# EXCISS_HVU.net
KiCad netlist of a schematic drawn in EAGLE
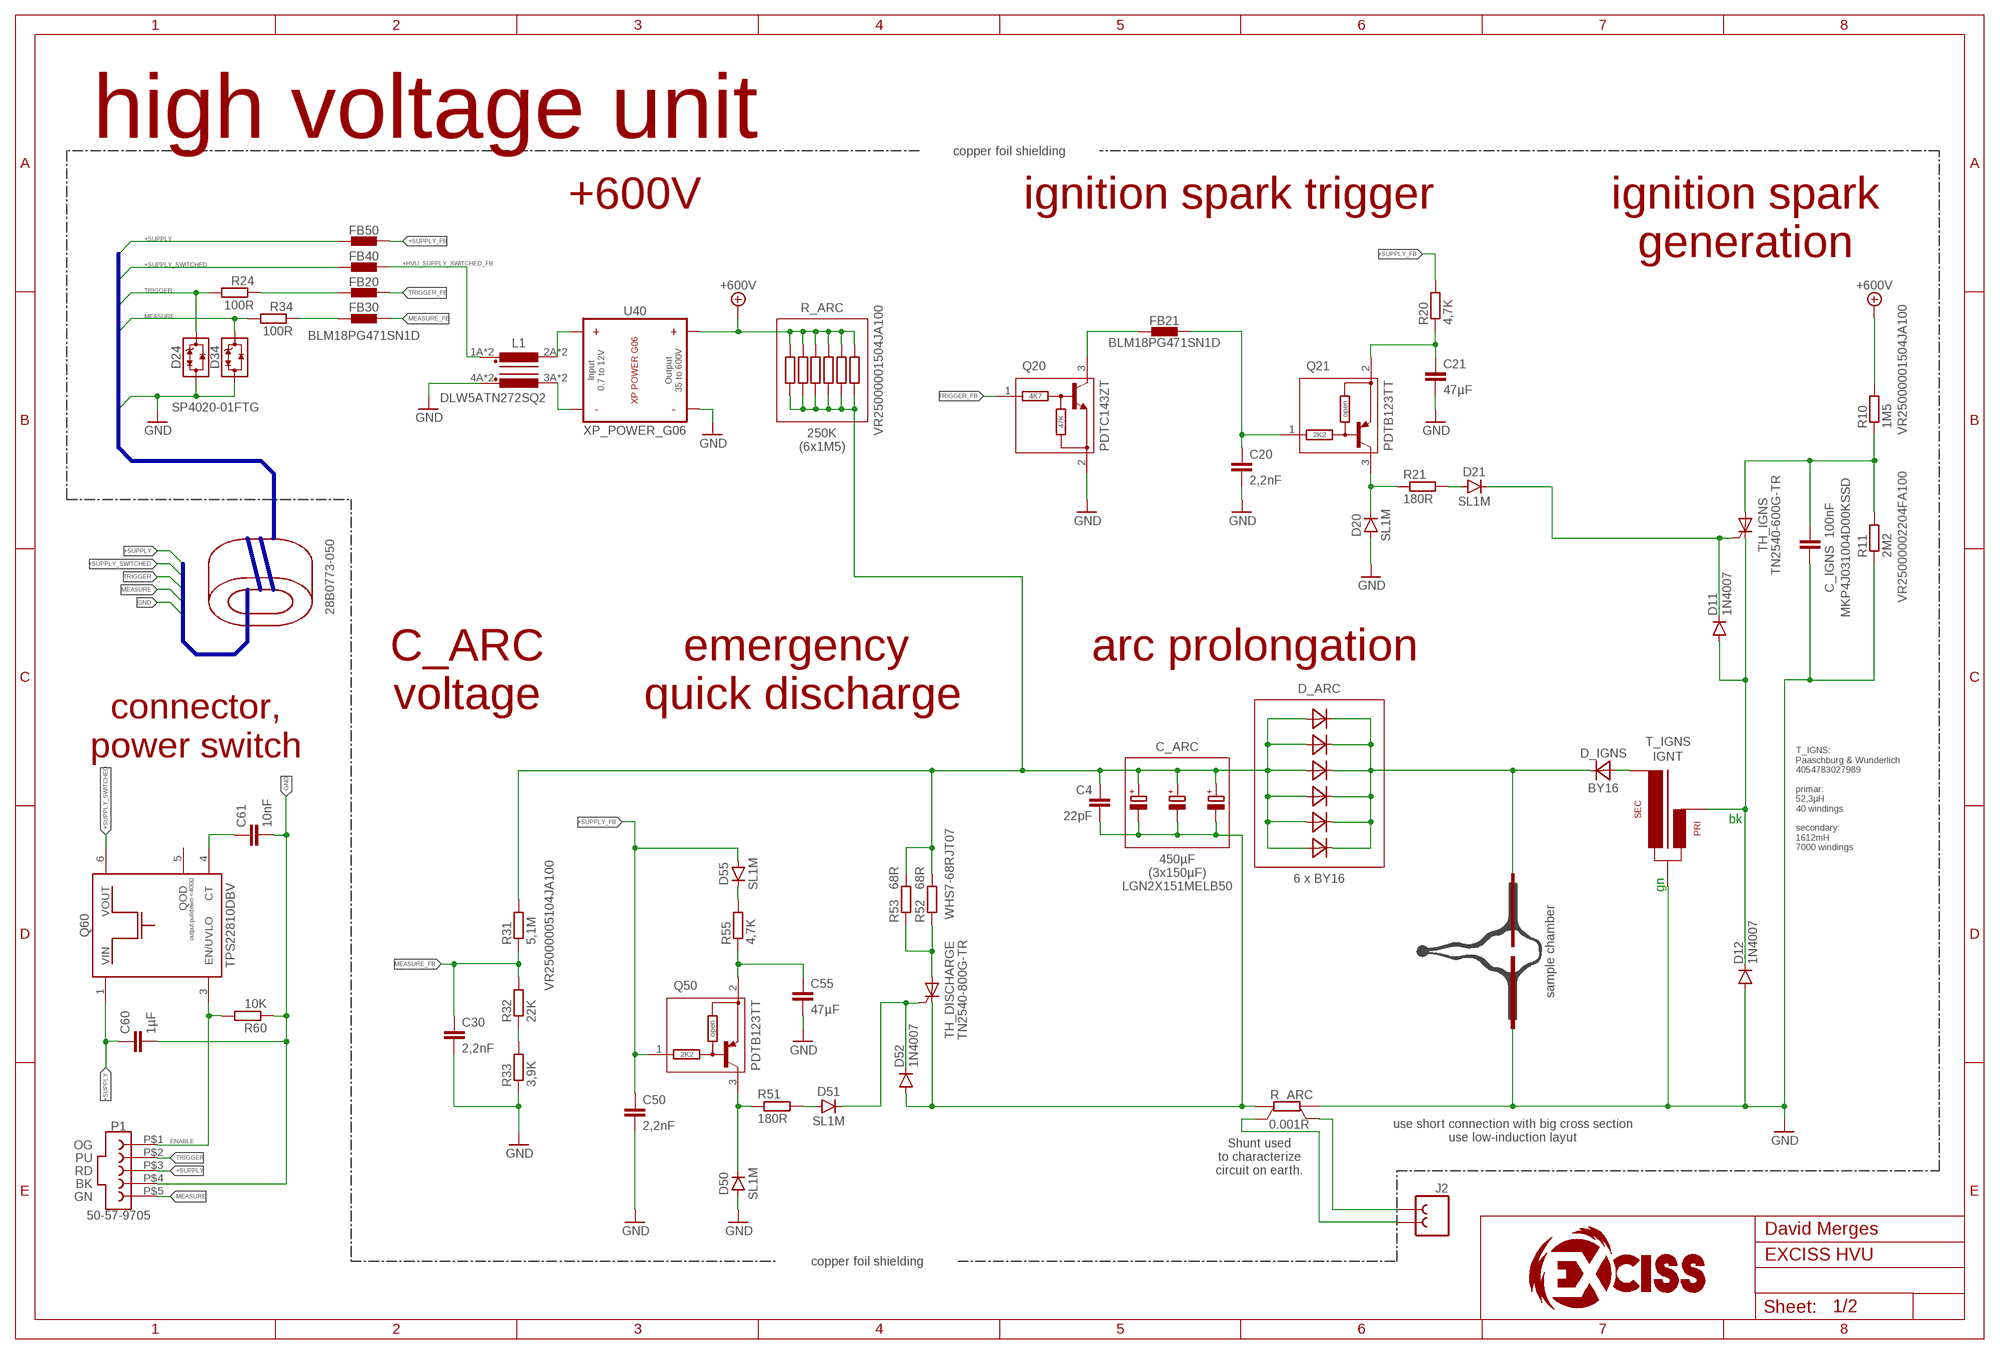
[diagram p0: schematic, sheet 1]

(export (version "E")
  (design (tool "Eeschema 10.0.6"))
  (components
    (comp (ref "C4")
      (value "22pF")
      (footprint "eagle-import:C0805")
      (libsource (lib "eagle-import") (part "C-EUC0805"))
    )
    (comp (ref "C20")
      (value "2,2nF")
      (footprint "eagle-import:C0805")
      (libsource (lib "eagle-import") (part "C-EUC0805"))
    )
    (comp (ref "C21")
      (value "47µF")
      (footprint "eagle-import:C1206")
      (libsource (lib "eagle-import") (part "C-EUC1206"))
    )
    (comp (ref "C30")
      (value "2,2nF")
      (footprint "eagle-import:C0805")
      (libsource (lib "eagle-import") (part "C-EUC0805"))
    )
    (comp (ref "C50")
      (value "2,2nF")
      (footprint "eagle-import:C0805")
      (libsource (lib "eagle-import") (part "C-EUC0805"))
    )
    (comp (ref "C55")
      (value "47µF")
      (footprint "eagle-import:C1206")
      (libsource (lib "eagle-import") (part "C-EUC1206"))
    )
    (comp (ref "C60")
      (value "1µF")
      (footprint "eagle-import:C0805")
      (libsource (lib "eagle-import") (part "C-EUC0805"))
    )
    (comp (ref "C61")
      (value "10nF")
      (footprint "eagle-import:C0603")
      (libsource (lib "eagle-import") (part "C-EUC0603"))
    )
    (comp (ref "C_ARC1")
      (value "150µF")
      (footprint "eagle-import:140CLH-1010")
      (libsource (lib "eagle-import") (part "CPOL-EU140CLH-1010"))
    )
    (comp (ref "C_ARC2")
      (value "150µF")
      (footprint "eagle-import:140CLH-1010")
      (libsource (lib "eagle-import") (part "CPOL-EU140CLH-1010"))
    )
    (comp (ref "C_ARC3")
      (value "150µF")
      (footprint "eagle-import:140CLH-1010")
      (libsource (lib "eagle-import") (part "CPOL-EU140CLH-1010"))
    )
    (comp (ref "C_IGNS")
      (value "100nF")
      (footprint "eagle-import:C025-024X044")
      (libsource (lib "eagle-import") (part "C-EU025-024X044"))
    )
    (comp (ref "D11")
      (value "1N4007")
      (footprint "eagle-import:DO41-10")
      (libsource (lib "eagle-import") (part "1N4007"))
    )
    (comp (ref "D12")
      (value "1N4007")
      (footprint "eagle-import:DO41-10")
      (libsource (lib "eagle-import") (part "1N4007"))
    )
    (comp (ref "D20")
      (value "SL1M")
      (footprint "eagle-import:SOD-123FL")
      (libsource (lib "eagle-import") (part "SL1M"))
    )
    (comp (ref "D21")
      (value "SL1M")
      (footprint "eagle-import:SOD-123FL")
      (libsource (lib "eagle-import") (part "SL1M"))
    )
    (comp (ref "D24")
      (value "SP4020-01FTG")
      (footprint "eagle-import:SOD-323")
      (libsource (lib "eagle-import") (part "SP4020-01FTG"))
    )
    (comp (ref "D34")
      (value "SP4020-01FTG")
      (footprint "eagle-import:SOD-323")
      (libsource (lib "eagle-import") (part "SP4020-01FTG"))
    )
    (comp (ref "D50")
      (value "SL1M")
      (footprint "eagle-import:SOD-123FL")
      (libsource (lib "eagle-import") (part "SL1M"))
    )
    (comp (ref "D51")
      (value "SL1M")
      (footprint "eagle-import:SOD-123FL")
      (libsource (lib "eagle-import") (part "SL1M"))
    )
    (comp (ref "D52")
      (value "1N4007")
      (footprint "eagle-import:DO41-10")
      (libsource (lib "eagle-import") (part "1N4007"))
    )
    (comp (ref "D55")
      (value "SL1M")
      (footprint "eagle-import:SOD-123FL")
      (libsource (lib "eagle-import") (part "SL1M"))
    )
    (comp (ref "D_ARC1")
      (value "BY16")
      (footprint "eagle-import:BY16")
      (libsource (lib "eagle-import") (part "BY16"))
    )
    (comp (ref "D_ARC2")
      (value "BY16")
      (footprint "eagle-import:BY16")
      (libsource (lib "eagle-import") (part "BY16"))
    )
    (comp (ref "D_ARC3")
      (value "BY16")
      (footprint "eagle-import:BY16")
      (libsource (lib "eagle-import") (part "BY16"))
    )
    (comp (ref "D_ARC4")
      (value "BY16")
      (footprint "eagle-import:BY16")
      (libsource (lib "eagle-import") (part "BY16"))
    )
    (comp (ref "D_ARC5")
      (value "BY16")
      (footprint "eagle-import:BY16")
      (libsource (lib "eagle-import") (part "BY16"))
    )
    (comp (ref "D_ARC6")
      (value "BY16")
      (footprint "eagle-import:BY16")
      (libsource (lib "eagle-import") (part "BY16"))
    )
    (comp (ref "D_IGNS")
      (value "BY16")
      (footprint "eagle-import:BY16")
      (libsource (lib "eagle-import") (part "BY16"))
    )
    (comp (ref "FB20")
      (value "BLM18PG471SN1D")
      (footprint "eagle-import:0402")
      (libsource (lib "eagle-import") (part "BLM15HB121SN1"))
    )
    (comp (ref "FB21")
      (value "BLM18PG471SN1D")
      (footprint "eagle-import:0402")
      (libsource (lib "eagle-import") (part "BLM15HB121SN1"))
    )
    (comp (ref "FB30")
      (value "BLM18PG471SN1D")
      (footprint "eagle-import:0402")
      (libsource (lib "eagle-import") (part "BLM15HB121SN1"))
    )
    (comp (ref "FB40")
      (value "BLM18PG471SN1D")
      (footprint "eagle-import:0402")
      (libsource (lib "eagle-import") (part "BLM15HB121SN1"))
    )
    (comp (ref "FB50")
      (value "BLM18PG471SN1D")
      (footprint "eagle-import:0402")
      (libsource (lib "eagle-import") (part "BLM15HB121SN1"))
    )
    (comp (ref "J2")
      (value "F02")
      (footprint "eagle-import:1X02")
      (libsource (lib "eagle-import") (part "F02"))
    )
    (comp (ref "L1")
      (value "DLW5ATN272SQ2")
      (footprint "eagle-import:DLW5AT")
      (libsource (lib "eagle-import") (part "DLW5ATN272SQ2"))
    )
    (comp (ref "P1")
      (value "50-57-9705")
      (footprint "eagle-import:DUMMY")
      (libsource (lib "eagle-import") (part "14-56-2054"))
    )
    (comp (ref "Q20")
      (value "PDTC143ZT")
      (footprint "eagle-import:SOT23-3")
      (libsource (lib "eagle-import") (part "PDTC143ZT"))
    )
    (comp (ref "Q21")
      (value "PDTB123TT")
      (footprint "eagle-import:SOT23-3")
      (libsource (lib "eagle-import") (part "PDTB123TT"))
    )
    (comp (ref "Q50")
      (value "PDTB123TT")
      (footprint "eagle-import:SOT23-3")
      (libsource (lib "eagle-import") (part "PDTB123TT"))
    )
    (comp (ref "Q60")
      (value "TPS22810DBV")
      (footprint "eagle-import:SOT23-6_DBV")
      (libsource (lib "eagle-import") (part "TPS22810DBV"))
    )
    (comp (ref "R10")
      (value "1M5")
      (footprint "eagle-import:0204_7")
      (libsource (lib "eagle-import") (part "R-EU_0204/7"))
    )
    (comp (ref "R11")
      (value "2M2")
      (footprint "eagle-import:0204_7")
      (libsource (lib "eagle-import") (part "R-EU_0204/7"))
    )
    (comp (ref "R20")
      (value "4,7K")
      (footprint "eagle-import:R0603")
      (libsource (lib "eagle-import") (part "R-EU_R0603"))
    )
    (comp (ref "R21")
      (value "180R")
      (footprint "eagle-import:R0603")
      (libsource (lib "eagle-import") (part "R-EU_R0603"))
    )
    (comp (ref "R24")
      (value "100R")
      (footprint "eagle-import:R0603")
      (libsource (lib "eagle-import") (part "R-EU_R0603"))
    )
    (comp (ref "R31")
      (value "5,1M")
      (footprint "eagle-import:0204_7")
      (libsource (lib "eagle-import") (part "R-EU_0204/7"))
    )
    (comp (ref "R32")
      (value "22K")
      (footprint "eagle-import:0204_7")
      (libsource (lib "eagle-import") (part "R-EU_0204/7"))
    )
    (comp (ref "R33")
      (value "3,9K")
      (footprint "eagle-import:0204_7")
      (libsource (lib "eagle-import") (part "R-EU_0204/7"))
    )
    (comp (ref "R34")
      (value "100R")
      (footprint "eagle-import:R0603")
      (libsource (lib "eagle-import") (part "R-EU_R0603"))
    )
    (comp (ref "R51")
      (value "180R")
      (footprint "eagle-import:R0603")
      (libsource (lib "eagle-import") (part "R-EU_R0603"))
    )
    (comp (ref "R52")
      (value "68R")
      (footprint "eagle-import:0204_7")
      (libsource (lib "eagle-import") (part "R-EU_0204/7"))
    )
    (comp (ref "R53")
      (value "68R")
      (footprint "eagle-import:0204_7")
      (libsource (lib "eagle-import") (part "R-EU_0204/7"))
    )
    (comp (ref "R55")
      (value "4,7K")
      (footprint "eagle-import:R0603")
      (libsource (lib "eagle-import") (part "R-EU_R0603"))
    )
    (comp (ref "R60")
      (value "10K")
      (footprint "eagle-import:R0805")
      (libsource (lib "eagle-import") (part "R-EU_R0805"))
    )
    (comp (ref "R_ARC")
      (value "0.001R")
      (footprint "eagle-import:SMV")
      (libsource (lib "eagle-import") (part "SMV"))
    )
    (comp (ref "R_ARC1")
      (value "1,5M")
      (footprint "eagle-import:0204_7")
      (libsource (lib "eagle-import") (part "R-EU_0204/7"))
    )
    (comp (ref "R_ARC2")
      (value "1,5M")
      (footprint "eagle-import:0204_7")
      (libsource (lib "eagle-import") (part "R-EU_0204/7"))
    )
    (comp (ref "R_ARC3")
      (value "1,5M")
      (footprint "eagle-import:0204_7")
      (libsource (lib "eagle-import") (part "R-EU_0204/7"))
    )
    (comp (ref "R_ARC4")
      (value "1,5M")
      (footprint "eagle-import:0204_7")
      (libsource (lib "eagle-import") (part "R-EU_0204/7"))
    )
    (comp (ref "R_ARC5")
      (value "1,5M")
      (footprint "eagle-import:0204_7")
      (libsource (lib "eagle-import") (part "R-EU_0204/7"))
    )
    (comp (ref "R_ARC6")
      (value "1,5M")
      (footprint "eagle-import:0204_7")
      (libsource (lib "eagle-import") (part "R-EU_0204/7"))
    )
    (comp (ref "TH_DISCHARGE")
      (value "TN2540-800G-TR")
      (footprint "eagle-import:D2PACK")
      (libsource (lib "eagle-import") (part "TN2540-600G-TR"))
    )
    (comp (ref "TH_IGNS")
      (value "TN2540-600G-TR")
      (footprint "eagle-import:D2PACK")
      (libsource (lib "eagle-import") (part "TN2540-600G-TR"))
    )
    (comp (ref "T_IGNS")
      (value "IGNT")
      (footprint "eagle-import:DUMMY")
      (libsource (lib "eagle-import") (part "IGNT"))
    )
    (comp (ref "U$2")
      (value "PROBENKAMMER")
      (footprint "eagle-import:DUMMY")
      (libsource (lib "eagle-import") (part "PROBENKAMMER"))
    )
    (comp (ref "U40")
      (value "XP_POWER_G06")
      (footprint "eagle-import:XP_POWER_G06")
      (libsource (lib "eagle-import") (part "XP_POWER_G06"))
    )
  )
  (nets
    (net (code "1") (name "+600V") (class "Default")
      (node (ref "R10") (pin "2") (pinfunction "2_2") (pintype "passive"))
      (node (ref "R_ARC1") (pin "2") (pinfunction "2_2") (pintype "passive"))
      (node (ref "R_ARC2") (pin "2") (pinfunction "2_2") (pintype "passive"))
      (node (ref "R_ARC3") (pin "2") (pinfunction "2_2") (pintype "passive"))
      (node (ref "R_ARC4") (pin "2") (pinfunction "2_2") (pintype "passive"))
      (node (ref "R_ARC5") (pin "2") (pinfunction "2_2") (pintype "passive"))
      (node (ref "R_ARC6") (pin "2") (pinfunction "2_2") (pintype "passive"))
      (node (ref "U40") (pin "3") (pinfunction "+VOUT_3") (pintype "passive"))
    )
    (net (code "2") (name "+HVU_SUPPLY_SWITCHED_FB") (class "Default")
      (node (ref "FB40") (pin "2") (pinfunction "2_2") (pintype "passive"))
      (node (ref "L1") (pin "1A") (pinfunction "1_1A") (pintype "passive"))
      (node (ref "L1") (pin "1B+") (pinfunction "1_1B+") (pintype "passive"))
    )
    (net (code "3") (name "+SUPPLY") (class "Default")
      (node (ref "C60") (pin "1") (pinfunction "1_1") (pintype "passive"))
      (node (ref "FB50") (pin "1") (pinfunction "1_1") (pintype "passive"))
      (node (ref "P1") (pin "P$3") (pinfunction "3_P$3") (pintype "passive"))
      (node (ref "Q60") (pin "1") (pinfunction "VIN_1") (pintype "power_in"))
    )
    (net (code "4") (name "+SUPPLY_FB") (class "Default")
      (node (ref "C50") (pin "1") (pinfunction "1_1") (pintype "passive"))
      (node (ref "D55") (pin "A") (pinfunction "A_A") (pintype "passive"))
      (node (ref "FB50") (pin "2") (pinfunction "2_2") (pintype "passive"))
      (node (ref "Q50") (pin "1") (pinfunction "B_1") (pintype "passive"))
      (node (ref "R20") (pin "2") (pinfunction "2_2") (pintype "passive"))
    )
    (net (code "5") (name "+SUPPLY_SWITCHED") (class "Default")
      (node (ref "FB40") (pin "1") (pinfunction "1_1") (pintype "passive"))
      (node (ref "Q60") (pin "6") (pinfunction "VOUT_6") (pintype "output"))
    )
    (net (code "7") (name "ENABLE") (class "Default")
      (node (ref "P1") (pin "P$1") (pinfunction "1_P$1") (pintype "passive"))
      (node (ref "Q60") (pin "3") (pinfunction "EN/UVLO_3") (pintype "input"))
      (node (ref "R60") (pin "2") (pinfunction "2_2") (pintype "passive"))
    )
    (net (code "8") (name "GND") (class "Default")
      (node (ref "C20") (pin "2") (pinfunction "2_2") (pintype "passive"))
      (node (ref "C21") (pin "2") (pinfunction "2_2") (pintype "passive"))
      (node (ref "C30") (pin "2") (pinfunction "2_2") (pintype "passive"))
      (node (ref "C50") (pin "2") (pinfunction "2_2") (pintype "passive"))
      (node (ref "C55") (pin "2") (pinfunction "2_2") (pintype "passive"))
      (node (ref "C60") (pin "2") (pinfunction "2_2") (pintype "passive"))
      (node (ref "C61") (pin "2") (pinfunction "2_2") (pintype "passive"))
      (node (ref "C_IGNS") (pin "2") (pinfunction "2_2") (pintype "passive"))
      (node (ref "D12") (pin "A") (pinfunction "A_A") (pintype "passive"))
      (node (ref "D20") (pin "A") (pinfunction "A_A") (pintype "passive"))
      (node (ref "D24") (pin "A") (pinfunction "2_A") (pintype "passive"))
      (node (ref "D34") (pin "A") (pinfunction "2_A") (pintype "passive"))
      (node (ref "D50") (pin "A") (pinfunction "A_A") (pintype "passive"))
      (node (ref "L1") (pin "4A") (pinfunction "4_4A") (pintype "passive"))
      (node (ref "L1") (pin "4B") (pinfunction "4_4B") (pintype "passive"))
      (node (ref "P1") (pin "P$4") (pinfunction "4_P$4") (pintype "passive"))
      (node (ref "Q20") (pin "2") (pinfunction "E_2") (pintype "passive"))
      (node (ref "R11") (pin "1") (pinfunction "1_1") (pintype "passive"))
      (node (ref "R33") (pin "1") (pinfunction "1_1") (pintype "passive"))
      (node (ref "R60") (pin "1") (pinfunction "1_1") (pintype "passive"))
      (node (ref "R_ARC") (pin "I1") (pinfunction "A_I1") (pintype "passive"))
      (node (ref "T_IGNS") (pin "P$1") (pinfunction "COM_P$1") (pintype "passive"))
      (node (ref "U$2") (pin "P$1") (pinfunction "P$1_P$1") (pintype "bidirectional"))
      (node (ref "U40") (pin "4") (pinfunction "-VOUT_4") (pintype "passive"))
    )
    (net (code "9") (name "MEASURE") (class "Default")
      (node (ref "D34") (pin "C") (pinfunction "1_C") (pintype "passive"))
      (node (ref "P1") (pin "P$5") (pinfunction "5_P$5") (pintype "passive"))
      (node (ref "R34") (pin "2") (pinfunction "2_2") (pintype "passive"))
    )
    (net (code "10") (name "MEASURE_FB") (class "Default")
      (node (ref "C30") (pin "1") (pinfunction "1_1") (pintype "passive"))
      (node (ref "FB30") (pin "2") (pinfunction "2_2") (pintype "passive"))
      (node (ref "R31") (pin "1") (pinfunction "1_1") (pintype "passive"))
      (node (ref "R32") (pin "2") (pinfunction "2_2") (pintype "passive"))
    )
    (net (code "11") (name "Net-(C4-Pad1)") (class "Default")
      (node (ref "C4") (pin "1") (pinfunction "1_1") (pintype "passive"))
      (node (ref "C_ARC1") (pin "+") (pinfunction "+_+") (pintype "passive"))
      (node (ref "C_ARC2") (pin "+") (pinfunction "+_+") (pintype "passive"))
      (node (ref "C_ARC3") (pin "+") (pinfunction "+_+") (pintype "passive"))
      (node (ref "D_ARC1") (pin "A") (pinfunction "A_A") (pintype "passive"))
      (node (ref "D_ARC2") (pin "A") (pinfunction "A_A") (pintype "passive"))
      (node (ref "D_ARC3") (pin "A") (pinfunction "A_A") (pintype "passive"))
      (node (ref "D_ARC4") (pin "A") (pinfunction "A_A") (pintype "passive"))
      (node (ref "D_ARC5") (pin "A") (pinfunction "A_A") (pintype "passive"))
      (node (ref "D_ARC6") (pin "A") (pinfunction "A_A") (pintype "passive"))
      (node (ref "R31") (pin "2") (pinfunction "2_2") (pintype "passive"))
      (node (ref "R52") (pin "2") (pinfunction "2_2") (pintype "passive"))
      (node (ref "R53") (pin "2") (pinfunction "2_2") (pintype "passive"))
      (node (ref "R_ARC1") (pin "1") (pinfunction "1_1") (pintype "passive"))
      (node (ref "R_ARC2") (pin "1") (pinfunction "1_1") (pintype "passive"))
      (node (ref "R_ARC3") (pin "1") (pinfunction "1_1") (pintype "passive"))
      (node (ref "R_ARC4") (pin "1") (pinfunction "1_1") (pintype "passive"))
      (node (ref "R_ARC5") (pin "1") (pinfunction "1_1") (pintype "passive"))
      (node (ref "R_ARC6") (pin "1") (pinfunction "1_1") (pintype "passive"))
    )
    (net (code "12") (name "Net-(D21-PadA)") (class "Default")
      (node (ref "D21") (pin "A") (pinfunction "A_A") (pintype "passive"))
      (node (ref "R21") (pin "2") (pinfunction "2_2") (pintype "passive"))
    )
    (net (code "13") (name "Net-(D51-PadA)") (class "Default")
      (node (ref "D51") (pin "A") (pinfunction "A_A") (pintype "passive"))
      (node (ref "R51") (pin "2") (pinfunction "2_2") (pintype "passive"))
    )
    (net (code "14") (name "Net-(D55-PadC)") (class "Default")
      (node (ref "D55") (pin "C") (pinfunction "C_C") (pintype "passive"))
      (node (ref "R55") (pin "2") (pinfunction "2_2") (pintype "passive"))
    )
    (net (code "15") (name "Net-(D_ARC1-PadC)") (class "Default")
      (node (ref "D_ARC1") (pin "C") (pinfunction "C_C") (pintype "passive"))
      (node (ref "D_ARC2") (pin "C") (pinfunction "C_C") (pintype "passive"))
      (node (ref "D_ARC3") (pin "C") (pinfunction "C_C") (pintype "passive"))
      (node (ref "D_ARC4") (pin "C") (pinfunction "C_C") (pintype "passive"))
      (node (ref "D_ARC5") (pin "C") (pinfunction "C_C") (pintype "passive"))
      (node (ref "D_ARC6") (pin "C") (pinfunction "C_C") (pintype "passive"))
      (node (ref "D_IGNS") (pin "C") (pinfunction "C_C") (pintype "passive"))
      (node (ref "U$2") (pin "P$2") (pinfunction "P$2_P$2") (pintype "bidirectional"))
    )
    (net (code "16") (name "Net-(FB20-Pad1)") (class "Default")
      (node (ref "FB20") (pin "1") (pinfunction "1_1") (pintype "passive"))
      (node (ref "R24") (pin "1") (pinfunction "1_1") (pintype "passive"))
    )
    (net (code "17") (name "Net-(FB30-Pad1)") (class "Default")
      (node (ref "FB30") (pin "1") (pinfunction "1_1") (pintype "passive"))
      (node (ref "R34") (pin "1") (pinfunction "1_1") (pintype "passive"))
    )
    (net (code "18") (name "Net-(Q20-C)") (class "Default")
      (node (ref "FB21") (pin "1") (pinfunction "1_1") (pintype "passive"))
      (node (ref "Q20") (pin "3") (pinfunction "C_3") (pintype "passive"))
    )
    (net (code "19") (name "Net-(Q21-B)") (class "Default")
      (node (ref "C20") (pin "1") (pinfunction "1_1") (pintype "passive"))
      (node (ref "FB21") (pin "2") (pinfunction "2_2") (pintype "passive"))
      (node (ref "Q21") (pin "1") (pinfunction "B_1") (pintype "passive"))
    )
    (net (code "20") (name "Net-(Q21-C)") (class "Default")
      (node (ref "D20") (pin "C") (pinfunction "C_C") (pintype "passive"))
      (node (ref "Q21") (pin "3") (pinfunction "C_3") (pintype "passive"))
      (node (ref "R21") (pin "1") (pinfunction "1_1") (pintype "passive"))
    )
    (net (code "21") (name "Net-(Q21-E)") (class "Default")
      (node (ref "C21") (pin "1") (pinfunction "1_1") (pintype "passive"))
      (node (ref "Q21") (pin "2") (pinfunction "E_2") (pintype "passive"))
      (node (ref "R20") (pin "1") (pinfunction "1_1") (pintype "passive"))
    )
    (net (code "22") (name "Net-(Q50-C)") (class "Default")
      (node (ref "D50") (pin "C") (pinfunction "C_C") (pintype "passive"))
      (node (ref "Q50") (pin "3") (pinfunction "C_3") (pintype "passive"))
      (node (ref "R51") (pin "1") (pinfunction "1_1") (pintype "passive"))
    )
    (net (code "23") (name "Net-(Q50-E)") (class "Default")
      (node (ref "C55") (pin "1") (pinfunction "1_1") (pintype "passive"))
      (node (ref "Q50") (pin "2") (pinfunction "E_2") (pintype "passive"))
      (node (ref "R55") (pin "1") (pinfunction "1_1") (pintype "passive"))
    )
    (net (code "24") (name "Net-(Q60A-CT)") (class "Default")
      (node (ref "C61") (pin "1") (pinfunction "1_1") (pintype "passive"))
      (node (ref "Q60") (pin "4") (pinfunction "CT_4") (pintype "output"))
    )
    (net (code "25") (name "Net-(R32-Pad1)") (class "Default")
      (node (ref "R32") (pin "1") (pinfunction "1_1") (pintype "passive"))
      (node (ref "R33") (pin "2") (pinfunction "2_2") (pintype "passive"))
    )
    (net (code "26") (name "Net-(R_ARC-B)") (class "Default")
      (node (ref "C4") (pin "2") (pinfunction "2_2") (pintype "passive"))
      (node (ref "C_ARC1") (pin "-") (pinfunction "-_-") (pintype "passive"))
      (node (ref "C_ARC2") (pin "-") (pinfunction "-_-") (pintype "passive"))
      (node (ref "C_ARC3") (pin "-") (pinfunction "-_-") (pintype "passive"))
      (node (ref "D52") (pin "A") (pinfunction "A_A") (pintype "passive"))
      (node (ref "R_ARC") (pin "I2") (pinfunction "B_I2") (pintype "passive"))
      (node (ref "TH_DISCHARGE") (pin "1") (pinfunction "C_1") (pintype "passive"))
    )
    (net (code "27") (name "Net-(R_ARC-SA)") (class "Default")
      (node (ref "J2") (pin "2") (pinfunction "2_2") (pintype "passive"))
      (node (ref "R_ARC") (pin "U1") (pinfunction "SA_U1") (pintype "passive"))
    )
    (net (code "28") (name "Net-(R_ARC-SB)") (class "Default")
      (node (ref "J2") (pin "1") (pinfunction "1_1") (pintype "passive"))
      (node (ref "R_ARC") (pin "U2") (pinfunction "SB_U2") (pintype "passive"))
    )
    (net (code "29") (name "Net-(TH_DISCHARGE-A)") (class "Default")
      (node (ref "R52") (pin "1") (pinfunction "1_1") (pintype "passive"))
      (node (ref "R53") (pin "1") (pinfunction "1_1") (pintype "passive"))
      (node (ref "TH_DISCHARGE") (pin "2") (pinfunction "A_2") (pintype "passive"))
    )
    (net (code "30") (name "Net-(TH_DISCHARGE-G)") (class "Default")
      (node (ref "D51") (pin "C") (pinfunction "C_C") (pintype "passive"))
      (node (ref "D52") (pin "C") (pinfunction "C_C") (pintype "passive"))
      (node (ref "TH_DISCHARGE") (pin "3") (pinfunction "G_3") (pintype "passive"))
    )
    (net (code "31") (name "Net-(TH_IGNS-A)") (class "Default")
      (node (ref "C_IGNS") (pin "1") (pinfunction "1_1") (pintype "passive"))
      (node (ref "R10") (pin "1") (pinfunction "1_1") (pintype "passive"))
      (node (ref "R11") (pin "2") (pinfunction "2_2") (pintype "passive"))
      (node (ref "TH_IGNS") (pin "2") (pinfunction "A_2") (pintype "passive"))
    )
    (net (code "32") (name "Net-(TH_IGNS-C)") (class "Default")
      (node (ref "D11") (pin "A") (pinfunction "A_A") (pintype "passive"))
      (node (ref "D12") (pin "C") (pinfunction "C_C") (pintype "passive"))
      (node (ref "TH_IGNS") (pin "1") (pinfunction "C_1") (pintype "passive"))
      (node (ref "T_IGNS") (pin "P$2") (pinfunction "PRI_P$2") (pintype "passive"))
    )
    (net (code "33") (name "Net-(TH_IGNS-G)") (class "Default")
      (node (ref "D11") (pin "C") (pinfunction "C_C") (pintype "passive"))
      (node (ref "D21") (pin "C") (pinfunction "C_C") (pintype "passive"))
      (node (ref "TH_IGNS") (pin "3") (pinfunction "G_3") (pintype "passive"))
    )
    (net (code "34") (name "Net-(T_IGNS-SEC)") (class "Default")
      (node (ref "D_IGNS") (pin "A") (pinfunction "A_A") (pintype "passive"))
      (node (ref "T_IGNS") (pin "P$3") (pinfunction "SEC_P$3") (pintype "passive"))
    )
    (net (code "35") (name "Net-(U40-+VIN)") (class "Default")
      (node (ref "L1") (pin "2A") (pinfunction "2_2A") (pintype "passive"))
      (node (ref "L1") (pin "2B") (pinfunction "2_2B") (pintype "passive"))
      (node (ref "U40") (pin "1") (pinfunction "+VIN_1") (pintype "passive"))
    )
    (net (code "36") (name "Net-(U40--VIN)") (class "Default")
      (node (ref "L1") (pin "3A") (pinfunction "3_3A") (pintype "passive"))
      (node (ref "L1") (pin "3B") (pinfunction "3_3B") (pintype "passive"))
      (node (ref "U40") (pin "2") (pinfunction "-VIN_2") (pintype "passive"))
    )
    (net (code "37") (name "TRIGGER") (class "Default")
      (node (ref "D24") (pin "C") (pinfunction "1_C") (pintype "passive"))
      (node (ref "P1") (pin "P$2") (pinfunction "2_P$2") (pintype "passive"))
      (node (ref "R24") (pin "2") (pinfunction "2_2") (pintype "passive"))
    )
    (net (code "38") (name "TRIGGER_FB") (class "Default")
      (node (ref "FB20") (pin "2") (pinfunction "2_2") (pintype "passive"))
      (node (ref "Q20") (pin "1") (pinfunction "B_1") (pintype "passive"))
    )
    (net (code "39") (name "unconnected-(Q60A-QOD-Pad5)") (class "Default")
      (node (ref "Q60") (pin "5") (pinfunction "QOD_5") (pintype "output"))
    )
  )
)
